# HV_Sense.net
KiCad netlist of a schematic drawn in Altium Designer
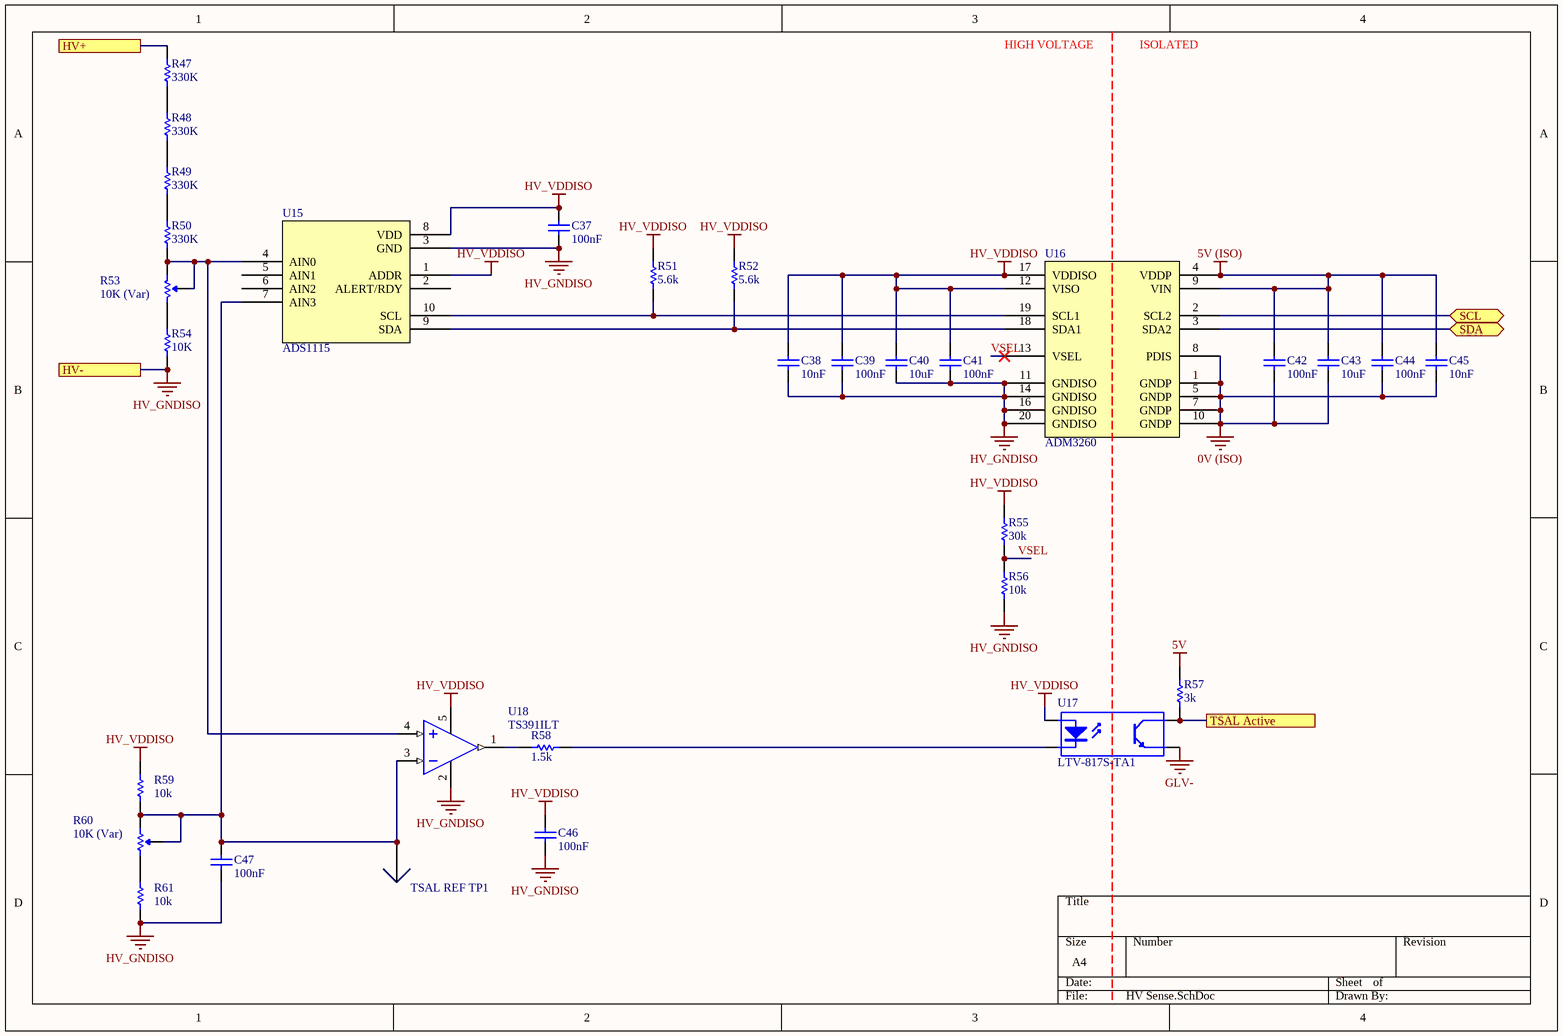
[diagram p0: HV Sense.SchDoc]

(export (version "E")
  (design (tool "Eeschema 10.0.6"))
  (components
    (comp (ref "C37")
      (value "100nF")
      (footprint "0805")
      (fields
        (field (name "PART NUMBER") "GCM21BR71H104KA37L")
        (field (name "TOLERANCE") "±10%")
        (field (name "MANUFACTURER") "muRata")
      )
      (libsource (lib "ts_20-standard-library") (part "Capacitor"))
    )
    (comp (ref "C38")
      (value "10nF")
      (footprint "0805")
      (fields
        (field (name "PART NUMBER") "GCM21BR71H103KA37L")
        (field (name "TOLERANCE") "10%")
        (field (name "MANUFACTURER") "muRata")
      )
      (libsource (lib "ts_20-standard-library") (part "Capacitor"))
    )
    (comp (ref "C39")
      (value "100nF")
      (footprint "0805")
      (fields
        (field (name "PART NUMBER") "GCM21BR71H104KA37L")
        (field (name "TOLERANCE") "±10%")
        (field (name "MANUFACTURER") "muRata")
      )
      (libsource (lib "ts_20-standard-library") (part "Capacitor"))
    )
    (comp (ref "C40")
      (value "10uF")
      (footprint "0805")
      (fields
        (field (name "PART NUMBER") "GRM21BR6YA106KE43L")
        (field (name "TOLERANCE") "10%")
        (field (name "MANUFACTURER") "muRata")
      )
      (libsource (lib "ts_20-standard-library") (part "Capacitor"))
    )
    (comp (ref "C41")
      (value "100nF")
      (footprint "0805")
      (fields
        (field (name "PART NUMBER") "GCM21BR71H104KA37L")
        (field (name "TOLERANCE") "±10%")
        (field (name "MANUFACTURER") "muRata")
      )
      (libsource (lib "ts_20-standard-library") (part "Capacitor"))
    )
    (comp (ref "C42")
      (value "100nF")
      (footprint "0805")
      (fields
        (field (name "PART NUMBER") "GCM21BR71H104KA37L")
        (field (name "TOLERANCE") "±10%")
        (field (name "MANUFACTURER") "muRata")
      )
      (libsource (lib "ts_20-standard-library") (part "Capacitor"))
    )
    (comp (ref "C43")
      (value "10uF")
      (footprint "0805")
      (fields
        (field (name "PART NUMBER") "GRM21BR6YA106KE43L")
        (field (name "TOLERANCE") "10%")
        (field (name "MANUFACTURER") "muRata")
      )
      (libsource (lib "ts_20-standard-library") (part "Capacitor"))
    )
    (comp (ref "C44")
      (value "100nF")
      (footprint "0805")
      (fields
        (field (name "PART NUMBER") "GCM21BR71H104KA37L")
        (field (name "TOLERANCE") "±10%")
        (field (name "MANUFACTURER") "muRata")
      )
      (libsource (lib "ts_20-standard-library") (part "Capacitor"))
    )
    (comp (ref "C45")
      (value "10nF")
      (footprint "0805")
      (fields
        (field (name "PART NUMBER") "GCM21BR71H103KA37L")
        (field (name "TOLERANCE") "10%")
        (field (name "MANUFACTURER") "muRata")
      )
      (libsource (lib "ts_20-standard-library") (part "Capacitor"))
    )
    (comp (ref "C46")
      (value "100nF")
      (footprint "0805")
      (fields
        (field (name "PART NUMBER") "GCM21BR71H104KA37L")
        (field (name "TOLERANCE") "±10%")
        (field (name "MANUFACTURER") "muRata")
      )
      (libsource (lib "ts_20-standard-library") (part "Capacitor"))
    )
    (comp (ref "C47")
      (value "100nF")
      (footprint "0805")
      (fields
        (field (name "PART NUMBER") "GCM21BR71H104KA37L")
        (field (name "TOLERANCE") "±10%")
        (field (name "MANUFACTURER") "muRata")
      )
      (libsource (lib "ts_20-standard-library") (part "Capacitor"))
    )
    (comp (ref "R47")
      (value "330K")
      (footprint "VB 0204")
      (fields
        (field (name "PART NUMBER") "MMA02040C3303FB300")
        (field (name "MANUFACTURER") "Vishay Beyschlag")
        (field (name "TOLERANCE") "0.01")
      )
      (libsource (lib "ts_20-standard-library") (part "Resistor"))
    )
    (comp (ref "R48")
      (value "330K")
      (footprint "VB 0204")
      (fields
        (field (name "PART NUMBER") "MMA02040C3303FB300")
        (field (name "MANUFACTURER") "Vishay Beyschlag")
        (field (name "TOLERANCE") "0.01")
      )
      (libsource (lib "ts_20-standard-library") (part "Resistor"))
    )
    (comp (ref "R49")
      (value "330K")
      (footprint "VB 0204")
      (fields
        (field (name "PART NUMBER") "MMA02040C3303FB300")
        (field (name "MANUFACTURER") "Vishay Beyschlag")
        (field (name "TOLERANCE") "0.01")
      )
      (libsource (lib "ts_20-standard-library") (part "Resistor"))
    )
    (comp (ref "R50")
      (value "330K")
      (footprint "VB 0204")
      (fields
        (field (name "PART NUMBER") "MMA02040C3303FB300")
        (field (name "MANUFACTURER") "Vishay Beyschlag")
        (field (name "TOLERANCE") "0.01")
      )
      (libsource (lib "ts_20-standard-library") (part "Resistor"))
    )
    (comp (ref "R51")
      (value "5.6k")
      (footprint "0805")
      (fields
        (field (name "PART NUMBER") "RC0805FR075K6L")
        (field (name "MANUFACTURER") "YAGEO")
        (field (name "TOLERANCE") "0.01")
      )
      (libsource (lib "ts_20-standard-library") (part "Resistor"))
    )
    (comp (ref "R52")
      (value "5.6k")
      (footprint "0805")
      (fields
        (field (name "PART NUMBER") "RC0805FR075K6L")
        (field (name "MANUFACTURER") "YAGEO")
        (field (name "TOLERANCE") "0.01")
      )
      (libsource (lib "ts_20-standard-library") (part "Resistor"))
    )
    (comp (ref "R53")
      (value "10K (Var)")
      (footprint "B 3296")
      (fields
        (field (name "PART NUMBER") "3296W-1-103LF")
        (field (name "MANUFACTURER") "Bournes Inc")
        (field (name "TOLERANCE") "0.1")
      )
      (libsource (lib "ts_20-standard-library") (part "Resistor (Potentiometer)"))
    )
    (comp (ref "R54")
      (value "10K")
      (footprint "VB 0204")
      (fields
        (field (name "PART NUMBER") "MMA02040C1002FB300")
        (field (name "MANUFACTURER") "Vishay Beyschlag")
        (field (name "TOLERANCE") "0.01")
      )
      (libsource (lib "ts_20-standard-library") (part "Resistor"))
    )
    (comp (ref "R55")
      (value "30k")
      (footprint "0805")
      (fields
        (field (name "PART NUMBER") "RC0805FR0730KL")
        (field (name "MANUFACTURER") "YAGEO")
        (field (name "TOLERANCE") "0.01")
      )
      (libsource (lib "ts_20-standard-library") (part "Resistor"))
    )
    (comp (ref "R56")
      (value "10k")
      (footprint "0805")
      (fields
        (field (name "PART NUMBER") "RC0805FR0710KL")
        (field (name "MANUFACTURER") "YAGEO")
        (field (name "TOLERANCE") "0.01")
      )
      (libsource (lib "ts_20-standard-library") (part "Resistor"))
    )
    (comp (ref "R57")
      (value "3k")
      (footprint "0805")
      (fields
        (field (name "PART NUMBER") "RC0805FR073KL")
        (field (name "MANUFACTURER") "YAGEO")
        (field (name "TOLERANCE") "0.01")
      )
      (libsource (lib "ts_20-standard-library") (part "Resistor"))
    )
    (comp (ref "R58")
      (value "1.5k")
      (footprint "0805")
      (fields
        (field (name "PART NUMBER") "RC0805FR071K5L")
        (field (name "MANUFACTURER") "YAGEO")
        (field (name "TOLERANCE") "0.01")
      )
      (libsource (lib "ts_20-standard-library") (part "Resistor"))
    )
    (comp (ref "R59")
      (value "10k")
      (footprint "0805")
      (fields
        (field (name "PART NUMBER") "RC0805FR0710KL")
        (field (name "MANUFACTURER") "YAGEO")
        (field (name "TOLERANCE") "0.01")
      )
      (libsource (lib "ts_20-standard-library") (part "Resistor"))
    )
    (comp (ref "R60")
      (value "10K (Var)")
      (footprint "B 3296")
      (fields
        (field (name "PART NUMBER") "3296W-1-103LF")
        (field (name "MANUFACTURER") "Bournes Inc")
        (field (name "TOLERANCE") "0.1")
      )
      (libsource (lib "ts_20-standard-library") (part "Resistor (Potentiometer)"))
    )
    (comp (ref "R61")
      (value "10k")
      (footprint "0805")
      (fields
        (field (name "PART NUMBER") "RC0805FR0710KL")
        (field (name "MANUFACTURER") "YAGEO")
        (field (name "TOLERANCE") "0.01")
      )
      (libsource (lib "ts_20-standard-library") (part "Resistor"))
    )
    (comp (ref "TSAL REF TP1")
      (value "0mm")
      (footprint "TH Test Point")
      (fields (field (name "PART NUMBER") "TH Test Point") (field (name "CONTACT") "NA"))
      (libsource (lib "ts_20-standard-connectors") (part "Test Point"))
    )
    (comp (ref "U15")
      (value "ADS1115")
      (footprint "TI 10-VSSOP")
      (description "16 Bit Analog to Digital Converter 2, 4 Input 1 Sigma-Delta 10-VSSOP")
      (fields
        (field (name "MANUFACTURER") "Texas Instruments")
        (field (name "DIGIKEY PART NUMBER") "296-38849-1-ND")
      )
      (libsource (lib "ts_20-standard-library") (part "ADS1115"))
    )
    (comp (ref "U16")
      (value "ADM3260")
      (footprint "AD 20-SSOP")
      (description "I²C Digital Isolator 2500Vrms 2 Channel 25kV/µs CMTI 20-SSOP (0.209\", 5.30mm Width)")
      (fields
        (field (name "MANUFACTURER") "Analog Devices")
        (field (name "DIGIKEY PART NUMBER") "ADM3260ARSZ-RL7CT-ND")
      )
      (libsource (lib "ts_20-standard-library") (part "ADM3260"))
    )
    (comp (ref "U17")
      (value "LTV-817S-TA1")
      (footprint "ON 4-SMD")
      (description "35V 50ma Optocoupler (VF=1.2V)")
      (fields
        (field (name "MANUFACTURER") "Lite-On Inc")
        (field (name "DIGIKEY PART NUMBER") "160-1893-2-ND")
      )
      (libsource (lib "ts_20-standard-library") (part "LTV-817S-TA1"))
    )
    (comp (ref "U18")
      (value "TS391ILT")
      (footprint "ON SOT-23-5")
      (description "IC COMP LO PWR SGL V SOT 23-5L")
      (fields
        (field (name "MANUFACTURER") "STMicroelectronics")
        (field (name "DIGIKEY PART NUMBER") "497-2275-2-ND")
      )
      (libsource (lib "ts_20-standard-library") (part "TS391ILT"))
    )
  )
  (nets
    (net (code "1") (name "/HV+") (class "Default")
      (node (ref "R47") (pin "2") (pinfunction "2_2") (pintype "passive"))
    )
    (net (code "2") (name "/SCL") (class "Default")
      (node (ref "U16") (pin "2") (pinfunction "SCL2_2") (pintype "passive"))
    )
    (net (code "3") (name "/SDA") (class "Default")
      (node (ref "U16") (pin "3") (pinfunction "SDA2_3") (pintype "passive"))
    )
    (net (code "4") (name "/TSAL Active") (class "Default")
      (node (ref "R57") (pin "1") (pinfunction "1_1") (pintype "passive"))
      (node (ref "U17") (pin "4") (pinfunction "C_4") (pintype "passive"))
    )
    (net (code "5") (name "/VSEL") (class "Default")
      (node (ref "R55") (pin "1") (pinfunction "1_1") (pintype "passive"))
      (node (ref "R56") (pin "2") (pinfunction "2_2") (pintype "passive"))
      (node (ref "U16") (pin "13") (pinfunction "VSEL_13") (pintype "passive"))
    )
    (net (code "6") (name "0V (ISO)") (class "Default")
      (node (ref "C42") (pin "1") (pinfunction "1_1") (pintype "passive"))
      (node (ref "C43") (pin "1") (pinfunction "1_1") (pintype "passive"))
      (node (ref "C44") (pin "1") (pinfunction "1_1") (pintype "passive"))
      (node (ref "C45") (pin "1") (pinfunction "1_1") (pintype "passive"))
      (node (ref "U16") (pin "1") (pinfunction "GNDP_1") (pintype "passive"))
      (node (ref "U16") (pin "10") (pinfunction "GNDP_10") (pintype "passive"))
      (node (ref "U16") (pin "5") (pinfunction "GNDP_5") (pintype "passive"))
      (node (ref "U16") (pin "7") (pinfunction "GNDP_7") (pintype "passive"))
      (node (ref "U16") (pin "8") (pinfunction "PDIS_8") (pintype "passive"))
    )
    (net (code "7") (name "5V") (class "Default")
      (node (ref "R57") (pin "2") (pinfunction "2_2") (pintype "passive"))
    )
    (net (code "8") (name "5V (ISO)") (class "Default")
      (node (ref "C42") (pin "2") (pinfunction "2_2") (pintype "passive"))
      (node (ref "C43") (pin "2") (pinfunction "2_2") (pintype "passive"))
      (node (ref "C44") (pin "2") (pinfunction "2_2") (pintype "passive"))
      (node (ref "C45") (pin "2") (pinfunction "2_2") (pintype "passive"))
      (node (ref "U16") (pin "4") (pinfunction "VDDP_4") (pintype "passive"))
      (node (ref "U16") (pin "9") (pinfunction "VIN_9") (pintype "passive"))
    )
    (net (code "9") (name "GLV-") (class "Default")
      (node (ref "U17") (pin "3") (pinfunction "E_3") (pintype "passive"))
    )
    (net (code "10") (name "HV_GNDISO") (class "Default")
      (node (ref "C37") (pin "1") (pinfunction "1_1") (pintype "passive"))
      (node (ref "C38") (pin "1") (pinfunction "1_1") (pintype "passive"))
      (node (ref "C39") (pin "1") (pinfunction "1_1") (pintype "passive"))
      (node (ref "C40") (pin "1") (pinfunction "1_1") (pintype "passive"))
      (node (ref "C41") (pin "1") (pinfunction "1_1") (pintype "passive"))
      (node (ref "C46") (pin "1") (pinfunction "1_1") (pintype "passive"))
      (node (ref "C47") (pin "1") (pinfunction "1_1") (pintype "passive"))
      (node (ref "R54") (pin "1") (pinfunction "1_1") (pintype "passive"))
      (node (ref "R56") (pin "1") (pinfunction "1_1") (pintype "passive"))
      (node (ref "R61") (pin "1") (pinfunction "1_1") (pintype "passive"))
      (node (ref "U15") (pin "3") (pinfunction "GND_3") (pintype "passive"))
      (node (ref "U16") (pin "11") (pinfunction "GNDISO_11") (pintype "passive"))
      (node (ref "U16") (pin "14") (pinfunction "GNDISO_14") (pintype "passive"))
      (node (ref "U16") (pin "16") (pinfunction "GNDISO_16") (pintype "passive"))
      (node (ref "U16") (pin "20") (pinfunction "GNDISO_20") (pintype "passive"))
      (node (ref "U18") (pin "2") (pinfunction "VCC-_2") (pintype "power_in"))
    )
    (net (code "11") (name "HV_VDDISO") (class "Default")
      (node (ref "C37") (pin "2") (pinfunction "2_2") (pintype "passive"))
      (node (ref "C38") (pin "2") (pinfunction "2_2") (pintype "passive"))
      (node (ref "C39") (pin "2") (pinfunction "2_2") (pintype "passive"))
      (node (ref "C40") (pin "2") (pinfunction "2_2") (pintype "passive"))
      (node (ref "C41") (pin "2") (pinfunction "2_2") (pintype "passive"))
      (node (ref "C46") (pin "2") (pinfunction "2_2") (pintype "passive"))
      (node (ref "R51") (pin "2") (pinfunction "2_2") (pintype "passive"))
      (node (ref "R52") (pin "2") (pinfunction "2_2") (pintype "passive"))
      (node (ref "R55") (pin "2") (pinfunction "2_2") (pintype "passive"))
      (node (ref "R59") (pin "2") (pinfunction "2_2") (pintype "passive"))
      (node (ref "U15") (pin "1") (pinfunction "ADDR_1") (pintype "passive"))
      (node (ref "U15") (pin "8") (pinfunction "VDD_8") (pintype "passive"))
      (node (ref "U16") (pin "12") (pinfunction "VISO_12") (pintype "passive"))
      (node (ref "U16") (pin "17") (pinfunction "VDDISO_17") (pintype "passive"))
      (node (ref "U17") (pin "1") (pinfunction "A_1") (pintype "passive"))
      (node (ref "U18") (pin "5") (pinfunction "VCC+_5") (pintype "power_in"))
    )
    (net (code "12") (name "Net-(R47-Pad1)") (class "Default")
      (node (ref "R47") (pin "1") (pinfunction "1_1") (pintype "passive"))
      (node (ref "R48") (pin "2") (pinfunction "2_2") (pintype "passive"))
    )
    (net (code "13") (name "Net-(R48-Pad1)") (class "Default")
      (node (ref "R48") (pin "1") (pinfunction "1_1") (pintype "passive"))
      (node (ref "R49") (pin "2") (pinfunction "2_2") (pintype "passive"))
    )
    (net (code "14") (name "Net-(R49-Pad1)") (class "Default")
      (node (ref "R49") (pin "1") (pinfunction "1_1") (pintype "passive"))
      (node (ref "R50") (pin "2") (pinfunction "2_2") (pintype "passive"))
    )
    (net (code "15") (name "Net-(R53-CCW)") (class "Default")
      (node (ref "R53") (pin "1") (pinfunction "CCW_1") (pintype "passive"))
      (node (ref "R54") (pin "2") (pinfunction "2_2") (pintype "passive"))
    )
    (net (code "16") (name "Net-(R53-CW)") (class "Default")
      (node (ref "R50") (pin "1") (pinfunction "1_1") (pintype "passive"))
      (node (ref "R53") (pin "2") (pinfunction "Wiper_2") (pintype "passive"))
      (node (ref "R53") (pin "3") (pinfunction "CW_3") (pintype "passive"))
      (node (ref "U15") (pin "4") (pinfunction "AIN0_4") (pintype "passive"))
      (node (ref "U18") (pin "4") (pinfunction "IIN+_4") (pintype "input"))
    )
    (net (code "17") (name "Net-(R60-CCW)") (class "Default")
      (node (ref "C47") (pin "2") (pinfunction "2_2") (pintype "passive"))
      (node (ref "R59") (pin "1") (pinfunction "1_1") (pintype "passive"))
      (node (ref "R60") (pin "1") (pinfunction "CCW_1") (pintype "passive"))
      (node (ref "R60") (pin "2") (pinfunction "Wiper_2") (pintype "passive"))
      (node (ref "TSAL REF TP1") (pin "1") (pinfunction "1_1") (pintype "passive"))
      (node (ref "U15") (pin "7") (pinfunction "AIN3_7") (pintype "passive"))
      (node (ref "U18") (pin "3") (pinfunction "IN-_3") (pintype "input"))
    )
    (net (code "18") (name "Net-(R60-CW)") (class "Default")
      (node (ref "R60") (pin "3") (pinfunction "CW_3") (pintype "passive"))
      (node (ref "R61") (pin "2") (pinfunction "2_2") (pintype "passive"))
    )
    (net (code "19") (name "Net-(U15-SCL)") (class "Default")
      (node (ref "R51") (pin "1") (pinfunction "1_1") (pintype "passive"))
      (node (ref "U15") (pin "10") (pinfunction "SCL_10") (pintype "passive"))
      (node (ref "U16") (pin "19") (pinfunction "SCL1_19") (pintype "passive"))
    )
    (net (code "20") (name "Net-(U15-SDA)") (class "Default")
      (node (ref "R52") (pin "1") (pinfunction "1_1") (pintype "passive"))
      (node (ref "U15") (pin "9") (pinfunction "SDA_9") (pintype "passive"))
      (node (ref "U16") (pin "18") (pinfunction "SDA1_18") (pintype "passive"))
    )
    (net (code "21") (name "Net-(U17-K)") (class "Default")
      (node (ref "R58") (pin "2") (pinfunction "2_2") (pintype "passive"))
      (node (ref "U17") (pin "2") (pinfunction "K_2") (pintype "passive"))
    )
    (net (code "22") (name "Net-(U18-OUT)") (class "Default")
      (node (ref "R58") (pin "1") (pinfunction "1_1") (pintype "passive"))
      (node (ref "U18") (pin "1") (pinfunction "OUT_1") (pintype "output"))
    )
    (net (code "23") (name "unconnected-(U15-AIN1-Pad5)") (class "Default")
      (node (ref "U15") (pin "5") (pinfunction "AIN1_5") (pintype "passive"))
    )
    (net (code "24") (name "unconnected-(U15-AIN2-Pad6)") (class "Default")
      (node (ref "U15") (pin "6") (pinfunction "AIN2_6") (pintype "passive"))
    )
    (net (code "25") (name "unconnected-(U15-ALERT{slash}RDY-Pad2)") (class "Default")
      (node (ref "U15") (pin "2") (pinfunction "ALERT/RDY_2") (pintype "passive"))
    )
  )
)
